# UltrasonicSensor.net
KiCad netlist of a schematic drawn in EAGLE
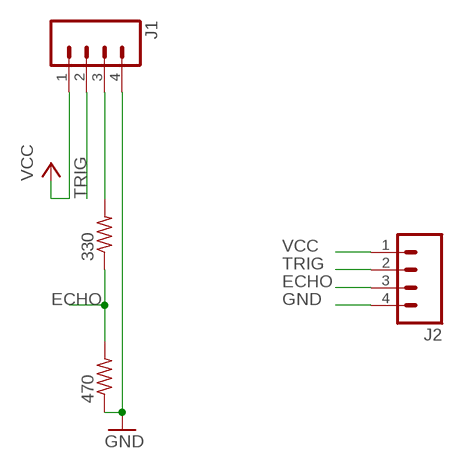
[diagram p0: schematic, sheet 1]

(export (version "E")
  (design (tool "Eeschema 10.0.6"))
  (components
    (comp (ref "330")
      (value "R-US_0204/5")
      (footprint "eagle-import:0204_5")
      (libsource (lib "eagle-import") (part "R-US_0204/5"))
    )
    (comp (ref "470")
      (value "R-US_0204/5")
      (footprint "eagle-import:0204_5")
      (libsource (lib "eagle-import") (part "R-US_0204/5"))
    )
    (comp (ref "J1")
      (value "M04NO_SILK_ALL_ROUND")
      (footprint "eagle-import:1X04_NO_SILK_ALL_ROUND")
      (libsource (lib "eagle-import") (part "M04NO_SILK_ALL_ROUND"))
    )
    (comp (ref "J2")
      (value "M04NO_SILK_ALL_ROUND")
      (footprint "eagle-import:1X04_NO_SILK_ALL_ROUND")
      (libsource (lib "eagle-import") (part "M04NO_SILK_ALL_ROUND"))
    )
  )
  (nets
    (net (code "1") (name "/ECHO") (class "Default")
      (node (ref "330") (pin "1") (pinfunction "1_1") (pintype "passive"))
      (node (ref "470") (pin "2") (pinfunction "2_2") (pintype "passive"))
      (node (ref "J2") (pin "3") (pinfunction "3_3") (pintype "passive"))
    )
    (net (code "2") (name "/TRIG") (class "Default")
      (node (ref "J1") (pin "2") (pinfunction "2_2") (pintype "passive"))
      (node (ref "J2") (pin "2") (pinfunction "2_2") (pintype "passive"))
    )
    (net (code "3") (name "GND") (class "Default")
      (node (ref "470") (pin "1") (pinfunction "1_1") (pintype "passive"))
      (node (ref "J1") (pin "4") (pinfunction "4_4") (pintype "passive"))
      (node (ref "J2") (pin "4") (pinfunction "4_4") (pintype "passive"))
    )
    (net (code "4") (name "Net-(330-Pad2)") (class "Default")
      (node (ref "330") (pin "2") (pinfunction "2_2") (pintype "passive"))
      (node (ref "J1") (pin "3") (pinfunction "3_3") (pintype "passive"))
    )
    (net (code "5") (name "VCC") (class "Default")
      (node (ref "J1") (pin "1") (pinfunction "1_1") (pintype "passive"))
      (node (ref "J2") (pin "1") (pinfunction "1_1") (pintype "passive"))
    )
  )
)
